# breeze_motor.net
KiCad netlist of a schematic drawn in Altium Designer
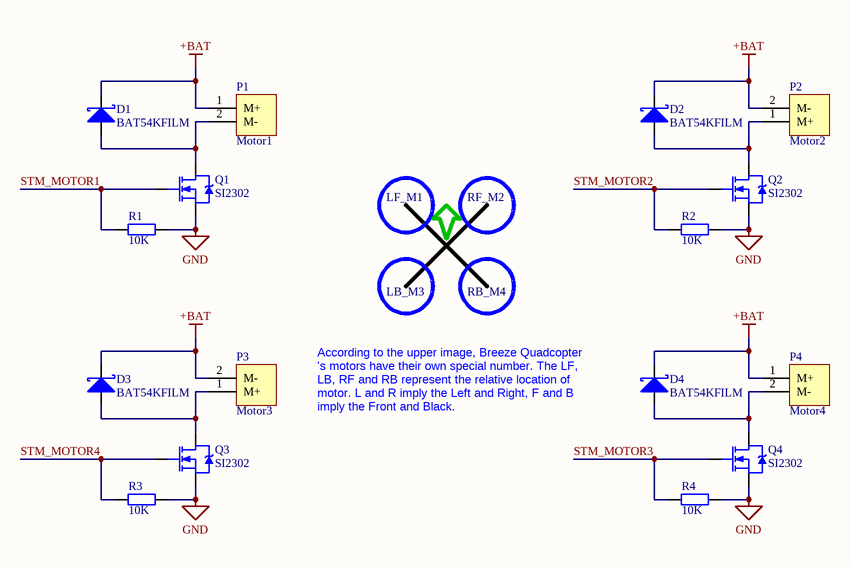
[diagram p0: breeze_motor.SchDoc]

(export (version "E")
  (design (tool "Eeschema 10.0.6"))
  (components
    (comp (ref "D1")
      (value "BAT54KFILM")
      (footprint "SOD-523")
      (description "Schottky Diode")
      (libsource (lib "breeze_design_library") (part "BAT54KFILM"))
    )
    (comp (ref "D2")
      (value "BAT54KFILM")
      (footprint "SOD-523")
      (description "Schottky Diode")
      (libsource (lib "breeze_design_library") (part "BAT54KFILM"))
    )
    (comp (ref "D3")
      (value "BAT54KFILM")
      (footprint "SOD-523")
      (description "Schottky Diode")
      (libsource (lib "breeze_design_library") (part "BAT54KFILM"))
    )
    (comp (ref "D4")
      (value "BAT54KFILM")
      (footprint "SOD-523")
      (description "Schottky Diode")
      (libsource (lib "breeze_design_library") (part "BAT54KFILM"))
    )
    (comp (ref "P1")
      (value "Motor1")
      (footprint "HDRM-1X2")
      (description "Motor Header")
      (libsource (lib "breeze_design_library") (part "Motor_A"))
    )
    (comp (ref "P2")
      (value "Motor2")
      (footprint "HDRM-1X2")
      (description "Motor Header")
      (libsource (lib "breeze_design_library") (part "Motor_B"))
    )
    (comp (ref "P3")
      (value "Motor3")
      (footprint "HDRM-1X2")
      (description "Motor Header")
      (libsource (lib "breeze_design_library") (part "Motor_B"))
    )
    (comp (ref "P4")
      (value "Motor4")
      (footprint "HDRM-1X2")
      (description "Motor Header")
      (libsource (lib "breeze_design_library") (part "Motor_A"))
    )
    (comp (ref "Q1")
      (value "SI2302")
      (footprint "SOT-23")
      (description "N-Channel Enhancement Mode Field Effect Transistor")
      (libsource (lib "breeze_design_library") (part "SI2302"))
    )
    (comp (ref "Q2")
      (value "SI2302")
      (footprint "SOT-23")
      (description "N-Channel Enhancement Mode Field Effect Transistor")
      (libsource (lib "breeze_design_library") (part "SI2302"))
    )
    (comp (ref "Q3")
      (value "SI2302")
      (footprint "SOT-23")
      (description "N-Channel Enhancement Mode Field Effect Transistor")
      (libsource (lib "breeze_design_library") (part "SI2302"))
    )
    (comp (ref "Q4")
      (value "SI2302")
      (footprint "SOT-23")
      (description "N-Channel Enhancement Mode Field Effect Transistor")
      (libsource (lib "breeze_design_library") (part "SI2302"))
    )
    (comp (ref "R1")
      (value "10K")
      (footprint "SMD-0603")
      (description "Resistor")
      (fields (field (name "Comment") "RES-0603"))
      (libsource (lib "breeze_design_library") (part "RES-0603"))
    )
    (comp (ref "R2")
      (value "10K")
      (footprint "SMD-0603")
      (description "Resistor")
      (fields (field (name "Comment") "RES-0603"))
      (libsource (lib "breeze_design_library") (part "RES-0603"))
    )
    (comp (ref "R3")
      (value "10K")
      (footprint "SMD-0603")
      (description "Resistor")
      (fields (field (name "Comment") "RES-0603"))
      (libsource (lib "breeze_design_library") (part "RES-0603"))
    )
    (comp (ref "R4")
      (value "10K")
      (footprint "SMD-0603")
      (description "Resistor")
      (fields (field (name "Comment") "RES-0603"))
      (libsource (lib "breeze_design_library") (part "RES-0603"))
    )
  )
  (nets
    (net (code "1") (name "+BAT") (class "Default")
      (node (ref "D1") (pin "2") (pinfunction "K_2") (pintype "passive"))
      (node (ref "D2") (pin "2") (pinfunction "K_2") (pintype "passive"))
      (node (ref "D3") (pin "2") (pinfunction "K_2") (pintype "passive"))
      (node (ref "D4") (pin "2") (pinfunction "K_2") (pintype "passive"))
      (node (ref "P1") (pin "1") (pinfunction "M+_1") (pintype "passive"))
      (node (ref "P2") (pin "2") (pinfunction "M-_2") (pintype "passive"))
      (node (ref "P3") (pin "2") (pinfunction "M-_2") (pintype "passive"))
      (node (ref "P4") (pin "1") (pinfunction "M+_1") (pintype "passive"))
    )
    (net (code "2") (name "/STM_MOTOR1") (class "Default")
      (node (ref "Q1") (pin "1") (pinfunction "G_1") (pintype "passive"))
      (node (ref "R1") (pin "1") (pinfunction "1_1") (pintype "passive"))
    )
    (net (code "3") (name "/STM_MOTOR2") (class "Default")
      (node (ref "Q2") (pin "1") (pinfunction "G_1") (pintype "passive"))
      (node (ref "R2") (pin "1") (pinfunction "1_1") (pintype "passive"))
    )
    (net (code "4") (name "/STM_MOTOR3") (class "Default")
      (node (ref "Q4") (pin "1") (pinfunction "G_1") (pintype "passive"))
      (node (ref "R4") (pin "1") (pinfunction "1_1") (pintype "passive"))
    )
    (net (code "5") (name "/STM_MOTOR4") (class "Default")
      (node (ref "Q3") (pin "1") (pinfunction "G_1") (pintype "passive"))
      (node (ref "R3") (pin "1") (pinfunction "1_1") (pintype "passive"))
    )
    (net (code "6") (name "GND") (class "Default")
      (node (ref "Q1") (pin "2") (pinfunction "S_2") (pintype "passive"))
      (node (ref "Q2") (pin "2") (pinfunction "S_2") (pintype "passive"))
      (node (ref "Q3") (pin "2") (pinfunction "S_2") (pintype "passive"))
      (node (ref "Q4") (pin "2") (pinfunction "S_2") (pintype "passive"))
      (node (ref "R1") (pin "2") (pinfunction "2_2") (pintype "passive"))
      (node (ref "R2") (pin "2") (pinfunction "2_2") (pintype "passive"))
      (node (ref "R3") (pin "2") (pinfunction "2_2") (pintype "passive"))
      (node (ref "R4") (pin "2") (pinfunction "2_2") (pintype "passive"))
    )
    (net (code "7") (name "Net-(D1-A)") (class "Default")
      (node (ref "D1") (pin "1") (pinfunction "A_1") (pintype "passive"))
      (node (ref "P1") (pin "2") (pinfunction "M-_2") (pintype "passive"))
      (node (ref "Q1") (pin "3") (pinfunction "D_3") (pintype "passive"))
    )
    (net (code "8") (name "Net-(D2-A)") (class "Default")
      (node (ref "D2") (pin "1") (pinfunction "A_1") (pintype "passive"))
      (node (ref "P2") (pin "1") (pinfunction "M+_1") (pintype "passive"))
      (node (ref "Q2") (pin "3") (pinfunction "D_3") (pintype "passive"))
    )
    (net (code "9") (name "Net-(D3-A)") (class "Default")
      (node (ref "D3") (pin "1") (pinfunction "A_1") (pintype "passive"))
      (node (ref "P3") (pin "1") (pinfunction "M+_1") (pintype "passive"))
      (node (ref "Q3") (pin "3") (pinfunction "D_3") (pintype "passive"))
    )
    (net (code "10") (name "Net-(D4-A)") (class "Default")
      (node (ref "D4") (pin "1") (pinfunction "A_1") (pintype "passive"))
      (node (ref "P4") (pin "2") (pinfunction "M-_2") (pintype "passive"))
      (node (ref "Q4") (pin "3") (pinfunction "D_3") (pintype "passive"))
    )
  )
)
